# CAN.net
KiCad netlist of a schematic drawn in Altium Designer
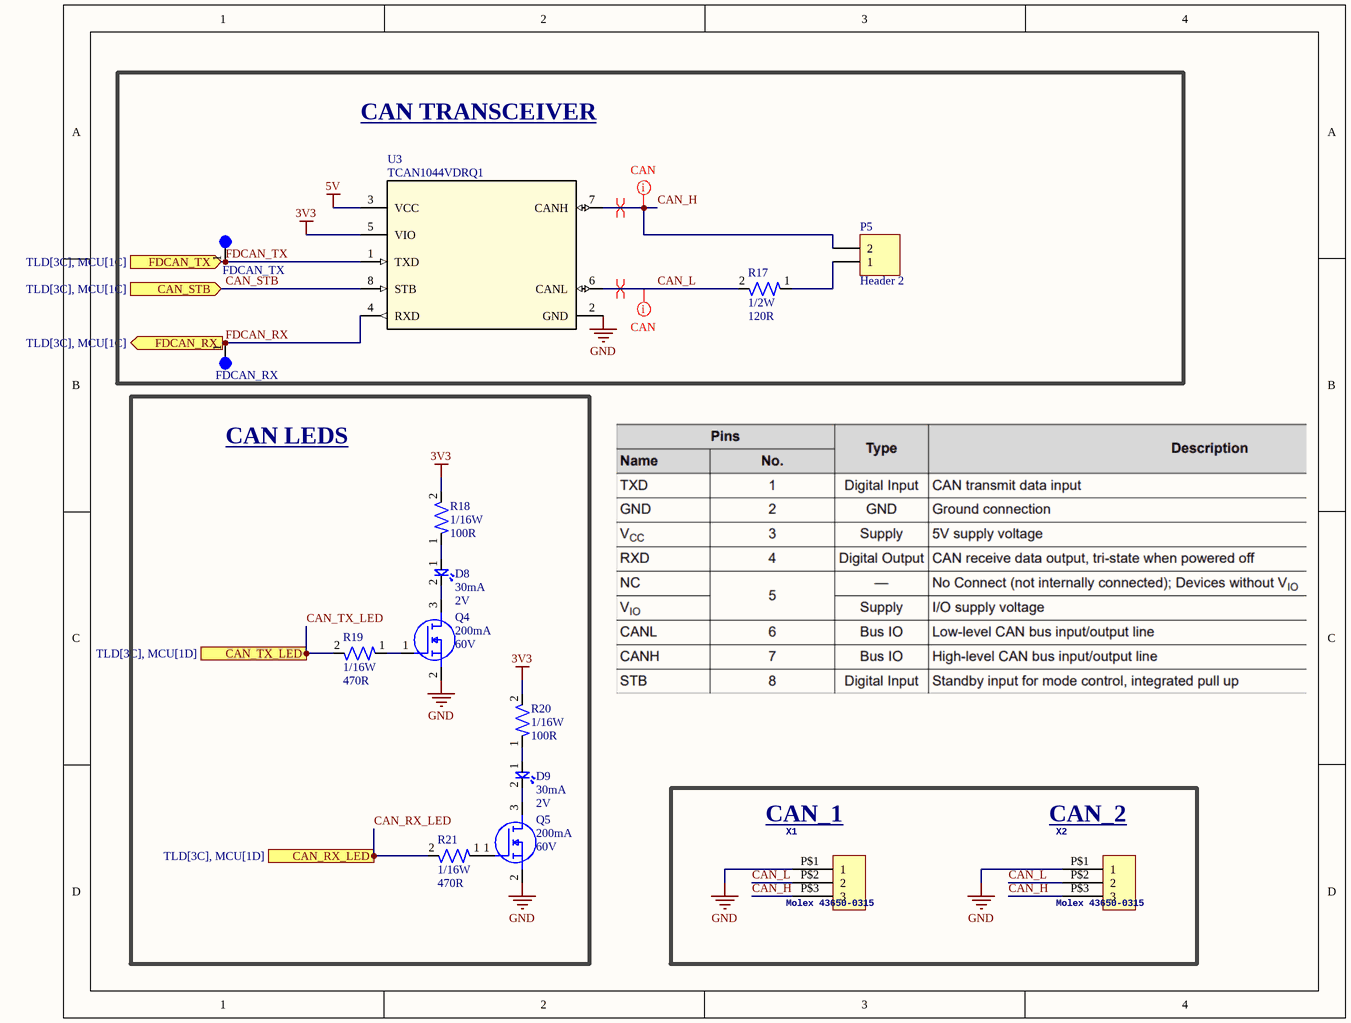
[diagram p0: CAN.SchDoc]

(export (version "E")
  (design (tool "Eeschema 10.0.6"))
  (components
    (comp (ref "D8")
      (value "BL-HKC36G-AV-TRB")
      (footprint "LED-0603")
      (description "LED YELLOW CLEAR 0603 SMD")
      (fields (field (name "FORWARD CURRENT") "30mA") (field (name "FORWARD VOLTAGE") "2V"))
      (libsource (lib "JLC_25") (part "LED-0001"))
    )
    (comp (ref "D9")
      (value "BL-HKC36G-AV-TRB")
      (footprint "LED-0603")
      (description "LED YELLOW CLEAR 0603 SMD")
      (fields (field (name "FORWARD CURRENT") "30mA") (field (name "FORWARD VOLTAGE") "2V"))
      (libsource (lib "JLC_25") (part "LED-0001"))
    )
    (comp (ref "FDCAN_RX")
      (value "5003")
      (footprint "TEST-POINT-0001")
      (description "Oranange PC Test Point, Miniature Phoisphor Bronze Silver Plating Through Hole Mounting Type")
      (libsource (lib "JLC_25") (part "TEST-POINT-0001"))
    )
    (comp (ref "FDCAN_TX")
      (value "5003")
      (footprint "TEST-POINT-0001")
      (description "Oranange PC Test Point, Miniature Phoisphor Bronze Silver Plating Through Hole Mounting Type")
      (libsource (lib "JLC_25") (part "TEST-POINT-0001"))
    )
    (comp (ref "P5")
      (value "Header 2")
      (footprint "HDR1X2")
      (description "Header, 2-Pin")
      (fields (field (name "PUBLISHER") "Altium Limited"))
      (libsource (lib "Miscellaneous Connectors") (part "Header 2"))
    )
    (comp (ref "Q4")
      (value "T2N7002AK,LM")
      (footprint "IC-SOT23-3")
      (description "MOSFET N-CH 60V 200MA SOT23")
      (fields (field (name "CONTINUOUS CURRENT") "200mA") (field (name "VOLTAGE") "60V"))
      (libsource (lib "JLC_25") (part "NMOS-200MA-0001"))
    )
    (comp (ref "Q5")
      (value "T2N7002AK,LM")
      (footprint "IC-SOT23-3")
      (description "MOSFET N-CH 60V 200MA SOT23")
      (fields (field (name "CONTINUOUS CURRENT") "200mA") (field (name "VOLTAGE") "60V"))
      (libsource (lib "JLC_25") (part "NMOS-200MA-0001"))
    )
    (comp (ref "R17")
      (value "RC1210FR-07120RL")
      (footprint "RES-1210")
      (description "RES 120 OHM 1% 1/2W 1210")
      (fields
        (field (name "TOLERANCE") "1%")
        (field (name "POWER") "1/2W")
        (field (name "RESISTANCE") "120R")
      )
      (libsource (lib "JLC_25") (part "RES-120-0001"))
    )
    (comp (ref "R18")
      (value "RC0402FR-07100RL")
      (footprint "RES-0402")
      (description "RES 100 OHM 1% 1/16W 0402")
      (fields
        (field (name "TOLERANCE") "1%")
        (field (name "POWER") "1/16W")
        (field (name "RESISTANCE") "100R")
      )
      (libsource (lib "JLC_25") (part "RES-100-0001"))
    )
    (comp (ref "R19")
      (value "RC0402FR-07470RL")
      (footprint "RES-0402")
      (description "RES 470 OHM 1% 1/16W 0402")
      (fields
        (field (name "TOLERANCE") "1%")
        (field (name "POWER") "1/16W")
        (field (name "RESISTANCE") "470R")
      )
      (libsource (lib "JLC_25") (part "RES-470-0001"))
    )
    (comp (ref "R20")
      (value "RC0402FR-07100RL")
      (footprint "RES-0402")
      (description "RES 100 OHM 1% 1/16W 0402")
      (fields
        (field (name "TOLERANCE") "1%")
        (field (name "POWER") "1/16W")
        (field (name "RESISTANCE") "100R")
      )
      (libsource (lib "JLC_25") (part "RES-100-0001"))
    )
    (comp (ref "R21")
      (value "RC0402FR-07470RL")
      (footprint "RES-0402")
      (description "RES 470 OHM 1% 1/16W 0402")
      (fields
        (field (name "TOLERANCE") "1%")
        (field (name "POWER") "1/16W")
        (field (name "RESISTANCE") "470R")
      )
      (libsource (lib "JLC_25") (part "RES-470-0001"))
    )
    (comp (ref "U3")
      (value "TCAN1044VDRQ1")
      (footprint "IC-8SOIC")
      (description "IC TRANSCEIVER 1/1 8SOIC")
      (libsource (lib "JLC_25") (part "IC-CAN-0001"))
    )
    (comp (ref "X1")
      (value "Molex 43650-0315")
      (footprint "43650-0315")
      (libsource (lib "Molex Microfit") (part "Micro-Fit Molex 3 Pin Vertical"))
    )
    (comp (ref "X2")
      (value "Molex 43650-0315")
      (footprint "43650-0315")
      (libsource (lib "Molex Microfit") (part "Micro-Fit Molex 3 Pin Vertical"))
    )
  )
  (nets
    (net (code "1") (name "/CAN_H") (class "Default")
      (node (ref "P5") (pin "2") (pinfunction "2_2") (pintype "passive"))
      (node (ref "U3") (pin "7") (pinfunction "CANH_7") (pintype "bidirectional"))
      (node (ref "X1") (pin "P$3") (pinfunction "3_P$3") (pintype "passive"))
      (node (ref "X2") (pin "P$3") (pinfunction "3_P$3") (pintype "passive"))
    )
    (net (code "2") (name "/CAN_L") (class "Default")
      (node (ref "R17") (pin "2") (pinfunction "2_2") (pintype "passive"))
      (node (ref "U3") (pin "6") (pinfunction "CANL_6") (pintype "bidirectional"))
      (node (ref "X1") (pin "P$2") (pinfunction "2_P$2") (pintype "passive"))
      (node (ref "X2") (pin "P$2") (pinfunction "2_P$2") (pintype "passive"))
    )
    (net (code "3") (name "/CAN_RX_LED") (class "Default")
      (node (ref "R21") (pin "2") (pinfunction "2_2") (pintype "passive"))
    )
    (net (code "4") (name "/CAN_STB") (class "Default")
      (node (ref "U3") (pin "8") (pinfunction "STB_8") (pintype "input"))
    )
    (net (code "5") (name "/CAN_TX_LED") (class "Default")
      (node (ref "R19") (pin "2") (pinfunction "2_2") (pintype "passive"))
    )
    (net (code "6") (name "/FDCAN_RX") (class "Default")
      (node (ref "FDCAN_RX") (pin "1") (pinfunction "0_1") (pintype "passive"))
      (node (ref "U3") (pin "4") (pinfunction "RXD_4") (pintype "output"))
    )
    (net (code "7") (name "/FDCAN_TX") (class "Default")
      (node (ref "FDCAN_TX") (pin "1") (pinfunction "0_1") (pintype "passive"))
      (node (ref "U3") (pin "1") (pinfunction "TXD_1") (pintype "input"))
    )
    (net (code "8") (name "3V3") (class "Default")
      (node (ref "R18") (pin "2") (pinfunction "2_2") (pintype "passive"))
      (node (ref "R20") (pin "2") (pinfunction "2_2") (pintype "passive"))
      (node (ref "U3") (pin "5") (pinfunction "VIO_5") (pintype "power_in"))
    )
    (net (code "9") (name "5V") (class "Default")
      (node (ref "U3") (pin "3") (pinfunction "VCC_3") (pintype "power_in"))
    )
    (net (code "10") (name "GND") (class "Default")
      (node (ref "Q4") (pin "2") (pinfunction "S_2") (pintype "passive"))
      (node (ref "Q5") (pin "2") (pinfunction "S_2") (pintype "passive"))
      (node (ref "U3") (pin "2") (pinfunction "GND_2") (pintype "power_in"))
      (node (ref "X1") (pin "P$1") (pinfunction "1_P$1") (pintype "passive"))
      (node (ref "X2") (pin "P$1") (pinfunction "1_P$1") (pintype "passive"))
    )
    (net (code "11") (name "Net-(D8-Pad1)") (class "Default")
      (node (ref "D8") (pin "1") (pinfunction "1_1") (pintype "passive"))
      (node (ref "R18") (pin "1") (pinfunction "1_1") (pintype "passive"))
    )
    (net (code "12") (name "Net-(D9-Pad1)") (class "Default")
      (node (ref "D9") (pin "1") (pinfunction "1_1") (pintype "passive"))
      (node (ref "R20") (pin "1") (pinfunction "1_1") (pintype "passive"))
    )
    (net (code "13") (name "Net-(P5-Pad1)") (class "Default")
      (node (ref "P5") (pin "1") (pinfunction "1_1") (pintype "passive"))
      (node (ref "R17") (pin "1") (pinfunction "1_1") (pintype "passive"))
    )
    (net (code "14") (name "Net-(Q4-D)") (class "Default")
      (node (ref "D8") (pin "2") (pinfunction "2_2") (pintype "passive"))
      (node (ref "Q4") (pin "3") (pinfunction "D_3") (pintype "passive"))
    )
    (net (code "15") (name "Net-(Q4-G)") (class "Default")
      (node (ref "Q4") (pin "1") (pinfunction "G_1") (pintype "passive"))
      (node (ref "R19") (pin "1") (pinfunction "1_1") (pintype "passive"))
    )
    (net (code "16") (name "Net-(Q5-D)") (class "Default")
      (node (ref "D9") (pin "2") (pinfunction "2_2") (pintype "passive"))
      (node (ref "Q5") (pin "3") (pinfunction "D_3") (pintype "passive"))
    )
    (net (code "17") (name "Net-(Q5-G)") (class "Default")
      (node (ref "Q5") (pin "1") (pinfunction "G_1") (pintype "passive"))
      (node (ref "R21") (pin "1") (pinfunction "1_1") (pintype "passive"))
    )
  )
)
